# CONNECTORS.net
KiCad netlist of a schematic drawn in Altium Designer
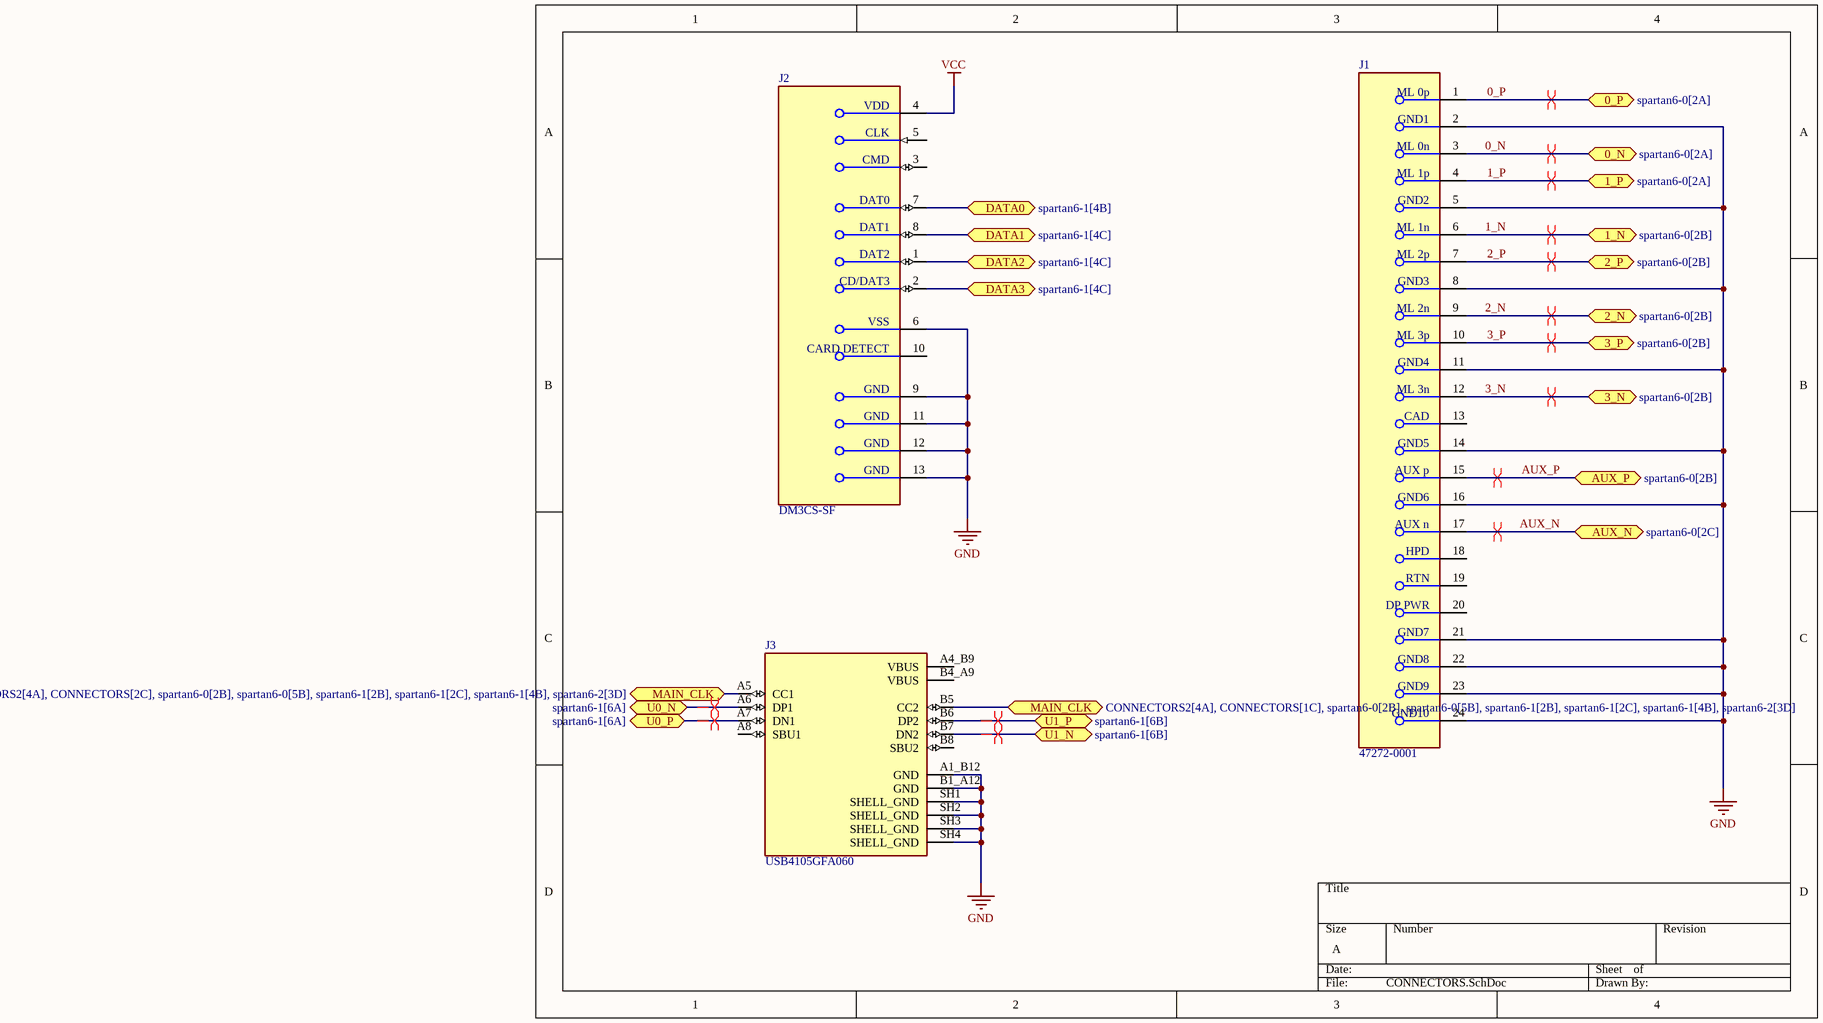
[diagram p0: CONNECTORS.SchDoc]

(export (version "E")
  (design (tool "Eeschema 10.0.6"))
  (components
    (comp (ref "J1")
      (value "47272-0001")
      (footprint "FP-47272-0001-MFG")
      (description "CONN RCPT DISPLAYPORT 20P SMD RA")
      (fields
        (field (name "MANUFACTURER") "Molex")
        (field (name "OCTOPART") "https://octopart.com/47272-0001-molex-5441289")
      )
      (libsource (lib "Altium Content Vault") (part "2afa8ceb06c8af4017661051ea5ebc1"))
    )
    (comp (ref "J2")
      (value "DM3CS-SF")
      (footprint "FP-DM3CS-SF-MFG")
      (description "CONN MICRO SD CARD HINGED TYPE")
      (libsource (lib "Altium Content Vault") (part "bac915de5305cfdd1ca301aae530106"))
    )
    (comp (ref "J3")
      (value "USB4105GFA060")
      (footprint "GCT_USB4105GFA060")
      (fields (field (name "MF") "{'manufacturer': u'GCT'}"))
      (libsource (lib "USB4105GFA060") (part "USB4105GFA060"))
    )
  )
  (nets
    (net (code "1") (name "/0_N") (class "Default")
      (node (ref "J1") (pin "3") (pinfunction "ML_0n_3") (pintype "passive"))
    )
    (net (code "2") (name "/0_P") (class "Default")
      (node (ref "J1") (pin "1") (pinfunction "ML_0p_1") (pintype "passive"))
    )
    (net (code "3") (name "/1_N") (class "Default")
      (node (ref "J1") (pin "6") (pinfunction "ML_1n_6") (pintype "passive"))
    )
    (net (code "4") (name "/1_P") (class "Default")
      (node (ref "J1") (pin "4") (pinfunction "ML_1p_4") (pintype "passive"))
    )
    (net (code "5") (name "/2_N") (class "Default")
      (node (ref "J1") (pin "9") (pinfunction "ML_2n_9") (pintype "passive"))
    )
    (net (code "6") (name "/2_P") (class "Default")
      (node (ref "J1") (pin "7") (pinfunction "ML_2p_7") (pintype "passive"))
    )
    (net (code "7") (name "/3_N") (class "Default")
      (node (ref "J1") (pin "12") (pinfunction "ML_3n_12") (pintype "passive"))
    )
    (net (code "8") (name "/3_P") (class "Default")
      (node (ref "J1") (pin "10") (pinfunction "ML_3p_10") (pintype "passive"))
    )
    (net (code "9") (name "/AUX_N") (class "Default")
      (node (ref "J1") (pin "17") (pinfunction "AUX_n_17") (pintype "passive"))
    )
    (net (code "10") (name "/AUX_P") (class "Default")
      (node (ref "J1") (pin "15") (pinfunction "AUX_p_15") (pintype "passive"))
    )
    (net (code "11") (name "/DATA0") (class "Default")
      (node (ref "J2") (pin "7") (pinfunction "DAT0_7") (pintype "bidirectional"))
    )
    (net (code "12") (name "/DATA1") (class "Default")
      (node (ref "J2") (pin "8") (pinfunction "DAT1_8") (pintype "bidirectional"))
    )
    (net (code "13") (name "/DATA2") (class "Default")
      (node (ref "J2") (pin "1") (pinfunction "DAT2_1") (pintype "bidirectional"))
    )
    (net (code "14") (name "/DATA3") (class "Default")
      (node (ref "J2") (pin "2") (pinfunction "CD/DAT3_2") (pintype "bidirectional"))
    )
    (net (code "15") (name "/MAIN_CLK") (class "Default")
      (node (ref "J3") (pin "A5") (pinfunction "CC1_A5") (pintype "bidirectional"))
      (node (ref "J3") (pin "B5") (pinfunction "CC2_B5") (pintype "bidirectional"))
    )
    (net (code "16") (name "/U0_N") (class "Default")
      (node (ref "J3") (pin "A6") (pinfunction "DP1_A6") (pintype "bidirectional"))
    )
    (net (code "17") (name "/U0_P") (class "Default")
      (node (ref "J3") (pin "A7") (pinfunction "DN1_A7") (pintype "bidirectional"))
    )
    (net (code "18") (name "/U1_N") (class "Default")
      (node (ref "J3") (pin "B7") (pinfunction "DN2_B7") (pintype "bidirectional"))
    )
    (net (code "19") (name "/U1_P") (class "Default")
      (node (ref "J3") (pin "B6") (pinfunction "DP2_B6") (pintype "bidirectional"))
    )
    (net (code "20") (name "GND") (class "Default")
      (node (ref "J1") (pin "11") (pinfunction "GND4_11") (pintype "power_in"))
      (node (ref "J1") (pin "14") (pinfunction "GND5_14") (pintype "power_in"))
      (node (ref "J1") (pin "16") (pinfunction "GND6_16") (pintype "power_in"))
      (node (ref "J1") (pin "2") (pinfunction "GND1_2") (pintype "power_in"))
      (node (ref "J1") (pin "21") (pinfunction "GND7_21") (pintype "power_in"))
      (node (ref "J1") (pin "22") (pinfunction "GND8_22") (pintype "power_in"))
      (node (ref "J1") (pin "23") (pinfunction "GND9_23") (pintype "power_in"))
      (node (ref "J1") (pin "24") (pinfunction "GND10_24") (pintype "power_in"))
      (node (ref "J1") (pin "5") (pinfunction "GND2_5") (pintype "power_in"))
      (node (ref "J1") (pin "8") (pinfunction "GND3_8") (pintype "power_in"))
      (node (ref "J2") (pin "11") (pinfunction "GND_11") (pintype "power_in"))
      (node (ref "J2") (pin "12") (pinfunction "GND_12") (pintype "power_in"))
      (node (ref "J2") (pin "13") (pinfunction "GND_13") (pintype "power_in"))
      (node (ref "J2") (pin "6") (pinfunction "VSS_6") (pintype "power_in"))
      (node (ref "J2") (pin "9") (pinfunction "GND_9") (pintype "power_in"))
      (node (ref "J3") (pin "A1_B12") (pinfunction "GND_A1_B12") (pintype "power_in"))
      (node (ref "J3") (pin "B1_A12") (pinfunction "GND_B1_A12") (pintype "power_in"))
      (node (ref "J3") (pin "SH1") (pinfunction "SHELL_GND_SH1") (pintype "power_in"))
      (node (ref "J3") (pin "SH2") (pinfunction "SHELL_GND_SH2") (pintype "power_in"))
      (node (ref "J3") (pin "SH3") (pinfunction "SHELL_GND_SH3") (pintype "power_in"))
      (node (ref "J3") (pin "SH4") (pinfunction "SHELL_GND_SH4") (pintype "power_in"))
    )
    (net (code "21") (name "VCC") (class "Default")
      (node (ref "J2") (pin "4") (pinfunction "VDD_4") (pintype "power_in"))
    )
    (net (code "22") (name "unconnected-(J1-CAD-Pad13)") (class "Default")
      (node (ref "J1") (pin "13") (pinfunction "CAD_13") (pintype "passive"))
    )
    (net (code "23") (name "unconnected-(J1-DP_PWR-Pad20)") (class "Default")
      (node (ref "J1") (pin "20") (pinfunction "DP_PWR_20") (pintype "passive"))
    )
    (net (code "24") (name "unconnected-(J1-HPD-Pad18)") (class "Default")
      (node (ref "J1") (pin "18") (pinfunction "HPD_18") (pintype "passive"))
    )
    (net (code "25") (name "unconnected-(J1-RTN-Pad19)") (class "Default")
      (node (ref "J1") (pin "19") (pinfunction "RTN_19") (pintype "passive"))
    )
    (net (code "26") (name "unconnected-(J2-CARD_DETECT-Pad10)") (class "Default")
      (node (ref "J2") (pin "10") (pinfunction "CARD_DETECT_10") (pintype "passive"))
    )
    (net (code "27") (name "unconnected-(J2-CLK-Pad5)") (class "Default")
      (node (ref "J2") (pin "5") (pinfunction "CLK_5") (pintype "input"))
    )
    (net (code "28") (name "unconnected-(J2-CMD-Pad3)") (class "Default")
      (node (ref "J2") (pin "3") (pinfunction "CMD_3") (pintype "bidirectional"))
    )
    (net (code "29") (name "unconnected-(J3-SBU1-PadA8)") (class "Default")
      (node (ref "J3") (pin "A8") (pinfunction "SBU1_A8") (pintype "bidirectional"))
    )
    (net (code "30") (name "unconnected-(J3-SBU2-PadB8)") (class "Default")
      (node (ref "J3") (pin "B8") (pinfunction "SBU2_B8") (pintype "bidirectional"))
    )
    (net (code "31") (name "unconnected-(J3-VBUS-PadA4_B9)") (class "Default")
      (node (ref "J3") (pin "A4_B9") (pinfunction "VBUS_A4_B9") (pintype "power_in"))
    )
    (net (code "32") (name "unconnected-(J3-VBUS-PadB4_A9)") (class "Default")
      (node (ref "J3") (pin "B4_A9") (pinfunction "VBUS_B4_A9") (pintype "power_in"))
    )
  )
)
